# Qwiic_pHat_for_Raspberry_Pi_v20.net
KiCad netlist of a schematic drawn in EAGLE
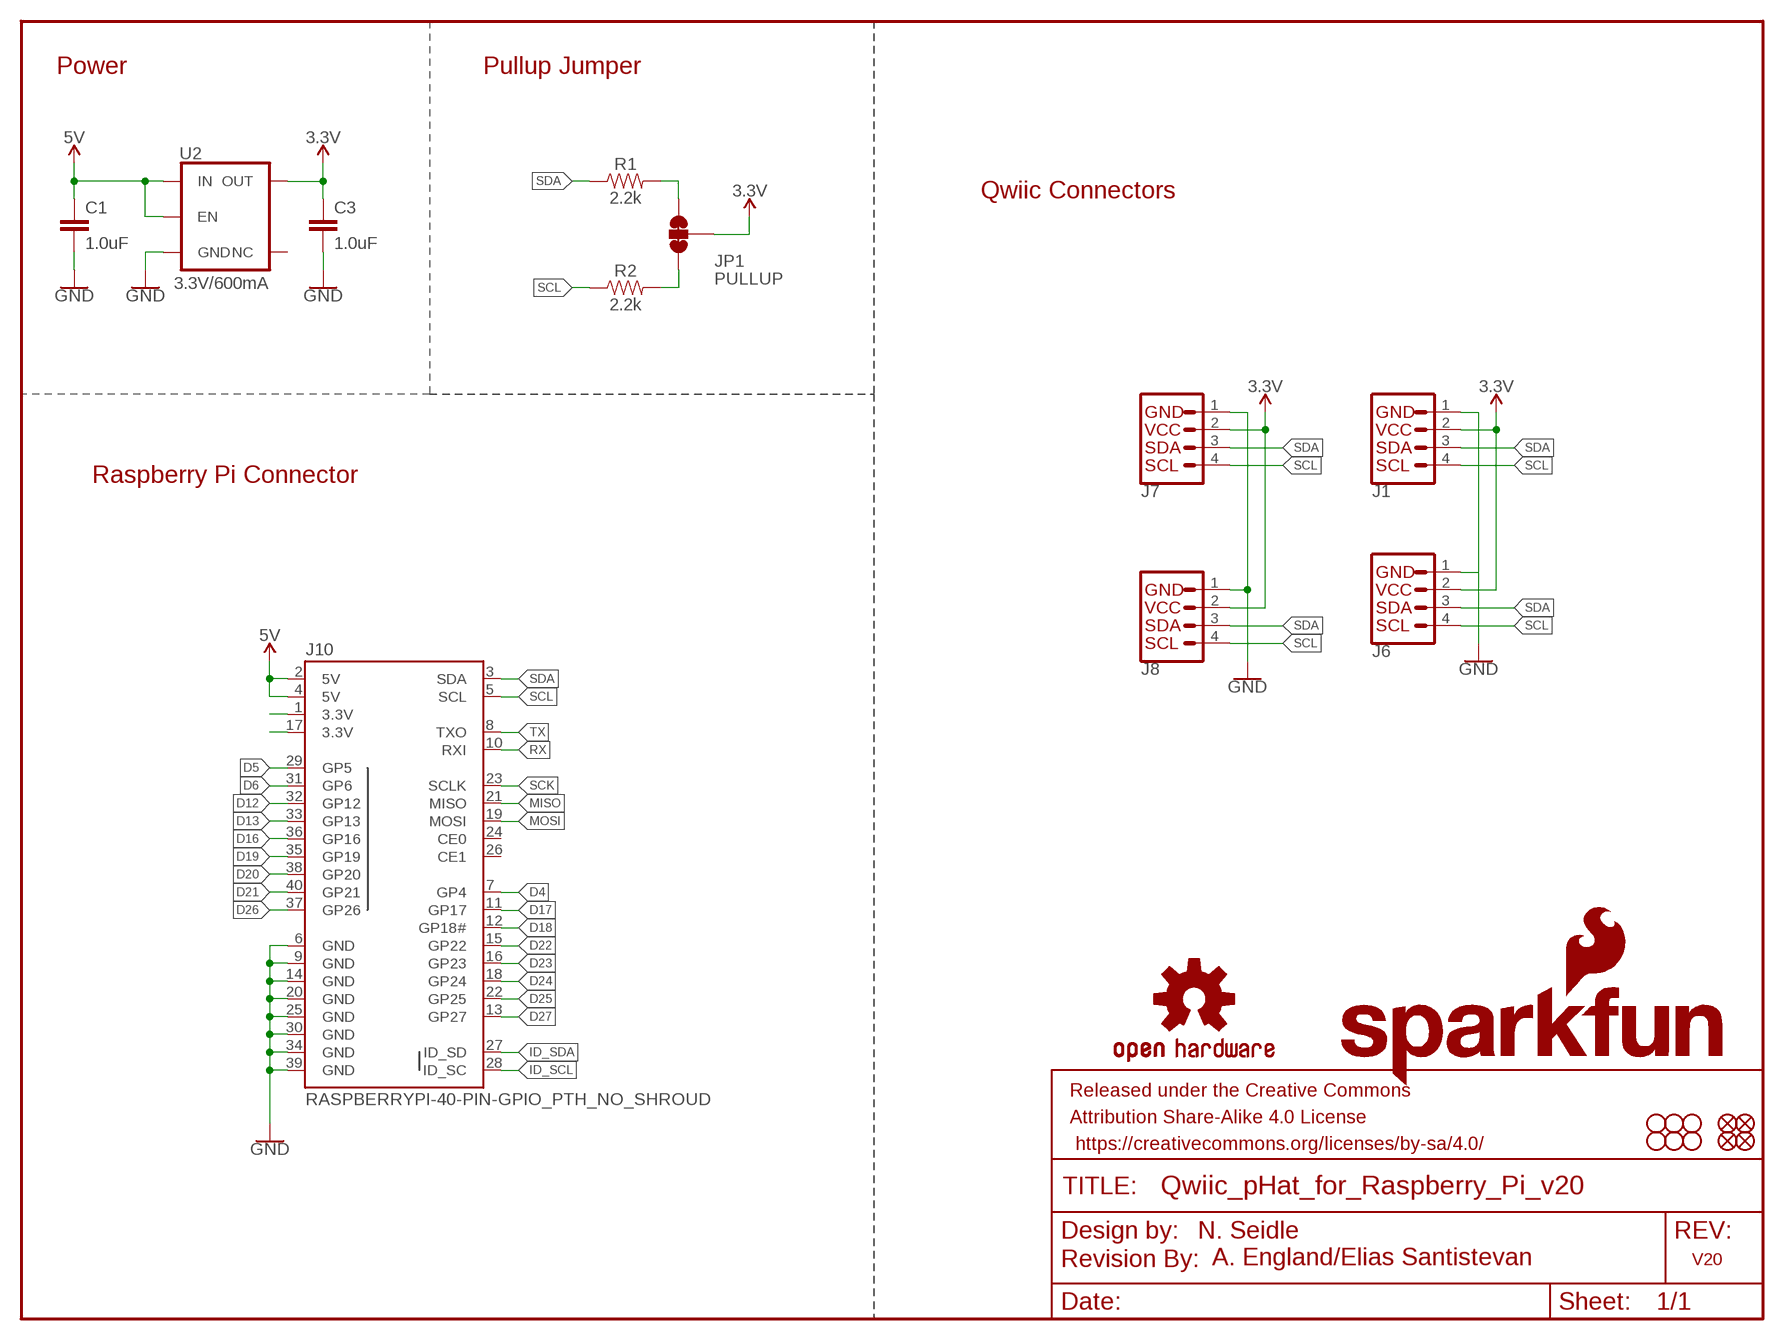
[diagram p0: schematic, sheet 1]

(export (version "E")
  (design (tool "Eeschema 10.0.6"))
  (components
    (comp (ref "C1")
      (value "1.0uF")
      (footprint "eagle-import:0603")
      (libsource (lib "eagle-import") (part "1.0UF-0603-16V-10%"))
    )
    (comp (ref "C3")
      (value "1.0uF")
      (footprint "eagle-import:0603")
      (libsource (lib "eagle-import") (part "1.0UF-0603-16V-10%"))
    )
    (comp (ref "FD1")
      (value "FIDUCIAL1X2")
      (footprint "eagle-import:FIDUCIAL-1X2")
      (libsource (lib "eagle-import") (part "FIDUCIAL1X2"))
    )
    (comp (ref "FD2")
      (value "FIDUCIAL1X2")
      (footprint "eagle-import:FIDUCIAL-1X2")
      (libsource (lib "eagle-import") (part "FIDUCIAL1X2"))
    )
    (comp (ref "FD3")
      (value "FIDUCIAL1X2")
      (footprint "eagle-import:FIDUCIAL-1X2")
      (libsource (lib "eagle-import") (part "FIDUCIAL1X2"))
    )
    (comp (ref "FD4")
      (value "FIDUCIAL1X2")
      (footprint "eagle-import:FIDUCIAL-1X2")
      (libsource (lib "eagle-import") (part "FIDUCIAL1X2"))
    )
    (comp (ref "FRAME1")
      (value "FRAME-LETTER")
      (footprint "eagle-import:CREATIVE_COMMONS")
      (libsource (lib "eagle-import") (part "FRAME-LETTER"))
    )
    (comp (ref "H1")
      (value "STAND-OFFTIGHT")
      (footprint "eagle-import:STAND-OFF-TIGHT")
      (libsource (lib "eagle-import") (part "STAND-OFFTIGHT"))
    )
    (comp (ref "H2")
      (value "STAND-OFFTIGHT")
      (footprint "eagle-import:STAND-OFF-TIGHT")
      (libsource (lib "eagle-import") (part "STAND-OFFTIGHT"))
    )
    (comp (ref "H3")
      (value "STAND-OFFTIGHT")
      (footprint "eagle-import:STAND-OFF-TIGHT")
      (libsource (lib "eagle-import") (part "STAND-OFFTIGHT"))
    )
    (comp (ref "H4")
      (value "STAND-OFFTIGHT")
      (footprint "eagle-import:STAND-OFF-TIGHT")
      (libsource (lib "eagle-import") (part "STAND-OFFTIGHT"))
    )
    (comp (ref "H5")
      (value "STAND-OFFTIGHT")
      (footprint "eagle-import:STAND-OFF-TIGHT")
      (libsource (lib "eagle-import") (part "STAND-OFFTIGHT"))
    )
    (comp (ref "H6")
      (value "STAND-OFFTIGHT")
      (footprint "eagle-import:STAND-OFF-TIGHT")
      (libsource (lib "eagle-import") (part "STAND-OFFTIGHT"))
    )
    (comp (ref "J1")
      (value "Qwiic Right Angle")
      (footprint "eagle-import:JST04_1MM_RA")
      (libsource (lib "eagle-import") (part "I2C_STANDARDQWIIC"))
    )
    (comp (ref "J6")
      (value "Qwiic Right Angle")
      (footprint "eagle-import:JST04_1MM_RA")
      (libsource (lib "eagle-import") (part "I2C_STANDARDQWIIC"))
    )
    (comp (ref "J7")
      (value "Qwiic Right Angle")
      (footprint "eagle-import:JST04_1MM_RA")
      (libsource (lib "eagle-import") (part "I2C_STANDARDQWIIC"))
    )
    (comp (ref "J8")
      (value "Qwiic Right Angle")
      (footprint "eagle-import:JST04_1MM_RA")
      (libsource (lib "eagle-import") (part "I2C_STANDARDQWIIC"))
    )
    (comp (ref "J10")
      (value "RASPBERRYPI-40-PIN-GPIO_PTH_NO_SHROUD")
      (footprint "eagle-import:2X20")
      (libsource (lib "eagle-import") (part "RASPBERRYPI-40-PIN-GPIO_PTH_NO_SHROUD"))
    )
    (comp (ref "JP1")
      (value "PULLUP")
      (footprint "eagle-import:SMT-JUMPER_3_2-NC_TRACE_NO-SILK")
      (libsource (lib "eagle-import") (part "JUMPER-SMT_3_2-NC_TRACE_NO-SILK"))
    )
    (comp (ref "LOGO1")
      (value "SFE_LOGO_NAME_FLAME.2_INCH")
      (footprint "eagle-import:SFE_LOGO_NAME_FLAME_.2")
      (libsource (lib "eagle-import") (part "SFE_LOGO_NAME_FLAME.2_INCH"))
    )
    (comp (ref "LOGO2")
      (value "REVISION")
      (footprint "eagle-import:REVISION")
      (libsource (lib "eagle-import") (part "REVISION"))
    )
    (comp (ref "LOGO3")
      (value "OSHW-LOGOS")
      (footprint "eagle-import:OSHW-LOGO-S")
      (libsource (lib "eagle-import") (part "OSHW-LOGOS"))
    )
    (comp (ref "R1")
      (value "2.2k")
      (footprint "eagle-import:0603")
      (libsource (lib "eagle-import") (part "2.2KOHM-0603-1/10W-1%"))
    )
    (comp (ref "R2")
      (value "2.2k")
      (footprint "eagle-import:0603")
      (libsource (lib "eagle-import") (part "2.2KOHM-0603-1/10W-1%"))
    )
    (comp (ref "U2")
      (value "3.3V/600mA")
      (footprint "eagle-import:SOT23-5")
      (libsource (lib "eagle-import") (part "V_REG_AP2112K-3.3V"))
    )
  )
  (nets
    (net (code "1") (name "3.3V") (class "Default")
      (node (ref "C3") (pin "1") (pinfunction "1_1") (pintype "passive"))
      (node (ref "J1") (pin "2") (pinfunction "2_2") (pintype "power_in"))
      (node (ref "J6") (pin "2") (pinfunction "2_2") (pintype "power_in"))
      (node (ref "J7") (pin "2") (pinfunction "2_2") (pintype "power_in"))
      (node (ref "J8") (pin "2") (pinfunction "2_2") (pintype "power_in"))
      (node (ref "JP1") (pin "2") (pinfunction "2_2") (pintype "passive"))
      (node (ref "U2") (pin "5") (pinfunction "OUT_5") (pintype "passive"))
    )
    (net (code "2") (name "5V") (class "Default")
      (node (ref "C1") (pin "1") (pinfunction "1_1") (pintype "passive"))
      (node (ref "J10") (pin "2") (pinfunction "5V_2") (pintype "power_in"))
      (node (ref "J10") (pin "4") (pinfunction "5V_4") (pintype "power_in"))
      (node (ref "U2") (pin "1") (pinfunction "IN_1") (pintype "input"))
      (node (ref "U2") (pin "3") (pinfunction "EN_3") (pintype "input"))
    )
    (net (code "3") (name "D4") (class "Default")
      (node (ref "J10") (pin "7") (pinfunction "GP4_7") (pintype "bidirectional"))
    )
    (net (code "4") (name "D5") (class "Default")
      (node (ref "J10") (pin "29") (pinfunction "GP5_29") (pintype "bidirectional"))
    )
    (net (code "5") (name "D6") (class "Default")
      (node (ref "J10") (pin "31") (pinfunction "GP6_31") (pintype "bidirectional"))
    )
    (net (code "6") (name "D12") (class "Default")
      (node (ref "J10") (pin "32") (pinfunction "GP12_32") (pintype "bidirectional"))
    )
    (net (code "7") (name "D13") (class "Default")
      (node (ref "J10") (pin "33") (pinfunction "GP13_33") (pintype "bidirectional"))
    )
    (net (code "8") (name "D16") (class "Default")
      (node (ref "J10") (pin "36") (pinfunction "GP16_36") (pintype "bidirectional"))
    )
    (net (code "9") (name "D17") (class "Default")
      (node (ref "J10") (pin "11") (pinfunction "GP17_11") (pintype "bidirectional"))
    )
    (net (code "10") (name "D18") (class "Default")
      (node (ref "J10") (pin "12") (pinfunction "GP18#_12") (pintype "bidirectional"))
    )
    (net (code "11") (name "D19") (class "Default")
      (node (ref "J10") (pin "35") (pinfunction "GP19_35") (pintype "bidirectional"))
    )
    (net (code "12") (name "D20") (class "Default")
      (node (ref "J10") (pin "38") (pinfunction "GP20_38") (pintype "bidirectional"))
    )
    (net (code "13") (name "D21") (class "Default")
      (node (ref "J10") (pin "40") (pinfunction "GP21_40") (pintype "bidirectional"))
    )
    (net (code "14") (name "D22") (class "Default")
      (node (ref "J10") (pin "15") (pinfunction "GP22_15") (pintype "bidirectional"))
    )
    (net (code "15") (name "D23") (class "Default")
      (node (ref "J10") (pin "16") (pinfunction "GP23_16") (pintype "bidirectional"))
    )
    (net (code "16") (name "D24") (class "Default")
      (node (ref "J10") (pin "18") (pinfunction "GP24_18") (pintype "bidirectional"))
    )
    (net (code "17") (name "D25") (class "Default")
      (node (ref "J10") (pin "22") (pinfunction "GP25_22") (pintype "bidirectional"))
    )
    (net (code "18") (name "D26") (class "Default")
      (node (ref "J10") (pin "37") (pinfunction "GP26_37") (pintype "bidirectional"))
    )
    (net (code "19") (name "D27") (class "Default")
      (node (ref "J10") (pin "13") (pinfunction "GP27_13") (pintype "bidirectional"))
    )
    (net (code "20") (name "GND") (class "Default")
      (node (ref "C1") (pin "2") (pinfunction "2_2") (pintype "passive"))
      (node (ref "C3") (pin "2") (pinfunction "2_2") (pintype "passive"))
      (node (ref "J1") (pin "1") (pinfunction "1_1") (pintype "power_in"))
      (node (ref "J10") (pin "14") (pinfunction "GND_14") (pintype "power_in"))
      (node (ref "J10") (pin "20") (pinfunction "GND_20") (pintype "power_in"))
      (node (ref "J10") (pin "25") (pinfunction "GND_25") (pintype "power_in"))
      (node (ref "J10") (pin "30") (pinfunction "GND_30") (pintype "power_in"))
      (node (ref "J10") (pin "34") (pinfunction "GND_34") (pintype "power_in"))
      (node (ref "J10") (pin "39") (pinfunction "GND_39") (pintype "power_in"))
      (node (ref "J10") (pin "6") (pinfunction "GND_6") (pintype "power_in"))
      (node (ref "J10") (pin "9") (pinfunction "GND_9") (pintype "power_in"))
      (node (ref "J6") (pin "1") (pinfunction "1_1") (pintype "power_in"))
      (node (ref "J7") (pin "1") (pinfunction "1_1") (pintype "power_in"))
      (node (ref "J8") (pin "1") (pinfunction "1_1") (pintype "power_in"))
      (node (ref "U2") (pin "2") (pinfunction "GND_2") (pintype "input"))
    )
    (net (code "21") (name "ID_SCL") (class "Default")
      (node (ref "J10") (pin "28") (pinfunction "ID_SC_28") (pintype "bidirectional"))
    )
    (net (code "22") (name "ID_SDA") (class "Default")
      (node (ref "J10") (pin "27") (pinfunction "ID_SD_27") (pintype "bidirectional"))
    )
    (net (code "23") (name "MISO") (class "Default")
      (node (ref "J10") (pin "21") (pinfunction "MISO_21") (pintype "input"))
    )
    (net (code "24") (name "MOSI") (class "Default")
      (node (ref "J10") (pin "19") (pinfunction "MOSI_19") (pintype "output"))
    )
    (net (code "25") (name "Net-(JP1-Pad1)") (class "Default")
      (node (ref "JP1") (pin "1") (pinfunction "1_1") (pintype "passive"))
      (node (ref "R2") (pin "2") (pinfunction "2_2") (pintype "passive"))
    )
    (net (code "26") (name "Net-(JP1-Pad3)") (class "Default")
      (node (ref "JP1") (pin "3") (pinfunction "3_3") (pintype "passive"))
      (node (ref "R1") (pin "2") (pinfunction "2_2") (pintype "passive"))
    )
    (net (code "27") (name "RX") (class "Default")
      (node (ref "J10") (pin "10") (pinfunction "RXI_10") (pintype "input"))
    )
    (net (code "28") (name "SCK") (class "Default")
      (node (ref "J10") (pin "23") (pinfunction "SCLK_23") (pintype "output"))
    )
    (net (code "29") (name "SCL") (class "Default")
      (node (ref "J1") (pin "4") (pinfunction "4_4") (pintype "passive"))
      (node (ref "J10") (pin "5") (pinfunction "SCL_5") (pintype "bidirectional"))
      (node (ref "J6") (pin "4") (pinfunction "4_4") (pintype "passive"))
      (node (ref "J7") (pin "4") (pinfunction "4_4") (pintype "passive"))
      (node (ref "J8") (pin "4") (pinfunction "4_4") (pintype "passive"))
      (node (ref "R2") (pin "1") (pinfunction "1_1") (pintype "passive"))
    )
    (net (code "30") (name "SDA") (class "Default")
      (node (ref "J1") (pin "3") (pinfunction "3_3") (pintype "passive"))
      (node (ref "J10") (pin "3") (pinfunction "SDA_3") (pintype "bidirectional"))
      (node (ref "J6") (pin "3") (pinfunction "3_3") (pintype "passive"))
      (node (ref "J7") (pin "3") (pinfunction "3_3") (pintype "passive"))
      (node (ref "J8") (pin "3") (pinfunction "3_3") (pintype "passive"))
      (node (ref "R1") (pin "1") (pinfunction "1_1") (pintype "passive"))
    )
    (net (code "31") (name "TX") (class "Default")
      (node (ref "J10") (pin "8") (pinfunction "TXO_8") (pintype "output"))
    )
    (net (code "32") (name "unconnected-(J10-3.3V-Pad1)") (class "Default")
      (node (ref "J10") (pin "1") (pinfunction "3.3V_1") (pintype "power_in"))
    )
    (net (code "33") (name "unconnected-(J10-3.3V-Pad17)") (class "Default")
      (node (ref "J10") (pin "17") (pinfunction "3.3V_17") (pintype "power_in"))
    )
    (net (code "34") (name "unconnected-(J10-CE0-Pad24)") (class "Default")
      (node (ref "J10") (pin "24") (pinfunction "CE0_24") (pintype "output"))
    )
    (net (code "35") (name "unconnected-(J10-CE1-Pad26)") (class "Default")
      (node (ref "J10") (pin "26") (pinfunction "CE1_26") (pintype "output"))
    )
    (net (code "36") (name "unconnected-(U2-NC-Pad4)") (class "Default")
      (node (ref "U2") (pin "4") (pinfunction "NC_4") (pintype "no_connect"))
    )
  )
)
